# Main.net
KiCad netlist of a schematic drawn in Altium Designer
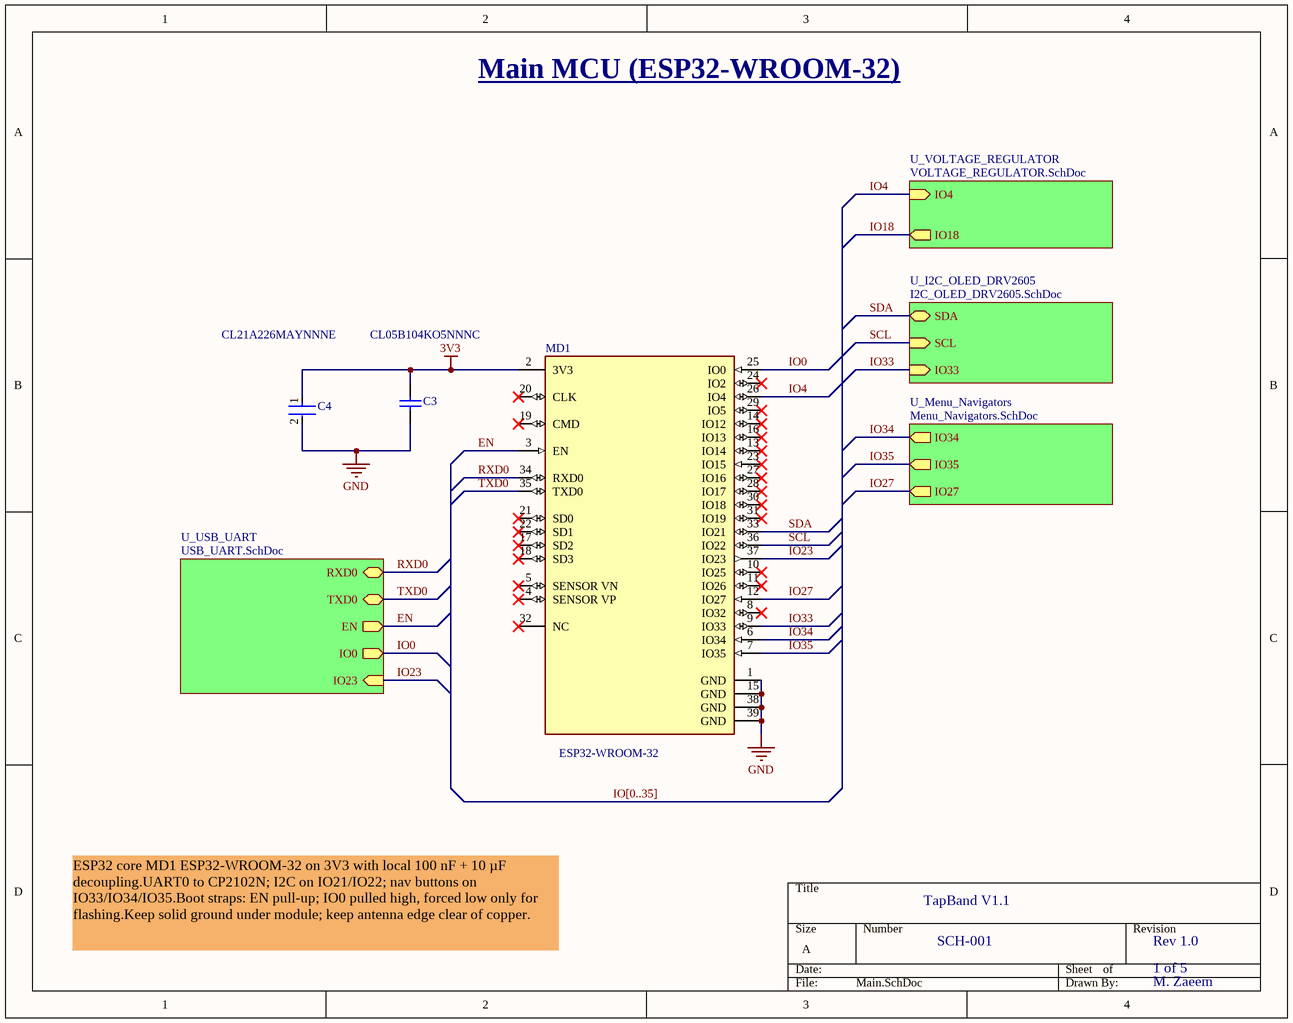
[diagram p0: Main.SchDoc]

(export (version "E")
  (design (tool "Eeschema 10.0.6"))
  (components
    (comp (ref "C3")
      (value "CL05B104KO5NNNC")
      (footprint "CAPC1050X55X23ML05T13")
      (description "Chip Capacitor, 100 nF, +/- 10%, 16 V, -55 to 125 degC, 0402 (1005 Metric), RoHS, Tape and Reel")
      (fields (field (name "MANUFACTURER") "Samsung Electro-Mechanics"))
      (libsource (lib "Altium Content Vault") (part "CAP-NP-2"))
    )
    (comp (ref "C4")
      (value "CL21A226MAYNNNE")
      (footprint "FP-CL21-IPC_C")
      (description "CL21 Series 0805 22uF 25V ±20% Tolerance X5R Multilayer Ceramic Chip Capacitor")
      (libsource (lib "Altium Content Vault") (part "b4654b650e69147ec39a6b967a45e02"))
    )
    (comp (ref "MD1")
      (value "ESP32-WROOM-32")
      (footprint "FP-ESP32-WROOM-32-MFG")
      (description "RX TXRX MOD WIFI SURFACE MOUNT")
      (libsource (lib "Altium Content Vault") (part "ee866abf0b6c51247b7f5cdebf2f250"))
    )
  )
  (nets
    (net (code "29") (name "/EN") (class "Default")
      (node (ref "MD1") (pin "3") (pinfunction "EN_3") (pintype "input"))
    )
    (net (code "30") (name "/IO0") (class "Default")
      (node (ref "MD1") (pin "25") (pinfunction "IO0_25") (pintype "input"))
    )
    (net (code "31") (name "/IO4") (class "Default")
      (node (ref "MD1") (pin "26") (pinfunction "IO4_26") (pintype "bidirectional"))
    )
    (net (code "33") (name "/IO23") (class "Default")
      (node (ref "MD1") (pin "37") (pinfunction "IO23_37") (pintype "output"))
    )
    (net (code "34") (name "/IO27") (class "Default")
      (node (ref "MD1") (pin "12") (pinfunction "IO27_12") (pintype "input"))
    )
    (net (code "35") (name "/IO33") (class "Default")
      (node (ref "MD1") (pin "9") (pinfunction "IO33_9") (pintype "bidirectional"))
    )
    (net (code "36") (name "/IO34") (class "Default")
      (node (ref "MD1") (pin "6") (pinfunction "IO34_6") (pintype "input"))
    )
    (net (code "37") (name "/IO35") (class "Default")
      (node (ref "MD1") (pin "7") (pinfunction "IO35_7") (pintype "input"))
    )
    (net (code "39") (name "/RXD0") (class "Default")
      (node (ref "MD1") (pin "34") (pinfunction "RXD0_34") (pintype "bidirectional"))
    )
    (net (code "40") (name "/SCL") (class "Default")
      (node (ref "MD1") (pin "36") (pinfunction "IO22_36") (pintype "bidirectional"))
    )
    (net (code "41") (name "/SDA") (class "Default")
      (node (ref "MD1") (pin "33") (pinfunction "IO21_33") (pintype "bidirectional"))
    )
    (net (code "42") (name "/TXD0") (class "Default")
      (node (ref "MD1") (pin "35") (pinfunction "TXD0_35") (pintype "bidirectional"))
    )
    (net (code "43") (name "3V3") (class "Default")
      (node (ref "C3") (pin "2") (pinfunction "2_2") (pintype "passive"))
      (node (ref "C4") (pin "1") (pinfunction "1_1") (pintype "passive"))
      (node (ref "MD1") (pin "2") (pinfunction "3V3_2") (pintype "power_in"))
    )
    (net (code "44") (name "GND") (class "Default")
      (node (ref "C3") (pin "1") (pinfunction "1_1") (pintype "passive"))
      (node (ref "C4") (pin "2") (pinfunction "2_2") (pintype "passive"))
      (node (ref "MD1") (pin "1") (pinfunction "GND_1") (pintype "power_in"))
      (node (ref "MD1") (pin "15") (pinfunction "GND_15") (pintype "power_in"))
      (node (ref "MD1") (pin "38") (pinfunction "GND_38") (pintype "power_in"))
      (node (ref "MD1") (pin "39") (pinfunction "GND_39") (pintype "power_in"))
    )
    (net (code "45") (name "unconnected-(MD1-CLK-Pad20)") (class "Default")
      (node (ref "MD1") (pin "20") (pinfunction "CLK_20") (pintype "bidirectional+no_connect"))
    )
    (net (code "46") (name "unconnected-(MD1-CMD-Pad19)") (class "Default")
      (node (ref "MD1") (pin "19") (pinfunction "CMD_19") (pintype "bidirectional+no_connect"))
    )
    (net (code "47") (name "unconnected-(MD1-IO2-Pad24)") (class "Default")
      (node (ref "MD1") (pin "24") (pinfunction "IO2_24") (pintype "bidirectional+no_connect"))
    )
    (net (code "48") (name "unconnected-(MD1-IO5-Pad29)") (class "Default")
      (node (ref "MD1") (pin "29") (pinfunction "IO5_29") (pintype "bidirectional+no_connect"))
    )
    (net (code "49") (name "unconnected-(MD1-IO12-Pad14)") (class "Default")
      (node (ref "MD1") (pin "14") (pinfunction "IO12_14") (pintype "bidirectional+no_connect"))
    )
    (net (code "50") (name "unconnected-(MD1-IO13-Pad16)") (class "Default")
      (node (ref "MD1") (pin "16") (pinfunction "IO13_16") (pintype "bidirectional+no_connect"))
    )
    (net (code "51") (name "unconnected-(MD1-IO14-Pad13)") (class "Default")
      (node (ref "MD1") (pin "13") (pinfunction "IO14_13") (pintype "bidirectional+no_connect"))
    )
    (net (code "52") (name "unconnected-(MD1-IO15-Pad23)") (class "Default")
      (node (ref "MD1") (pin "23") (pinfunction "IO15_23") (pintype "input+no_connect"))
    )
    (net (code "53") (name "unconnected-(MD1-IO16-Pad27)") (class "Default")
      (node (ref "MD1") (pin "27") (pinfunction "IO16_27") (pintype "bidirectional+no_connect"))
    )
    (net (code "54") (name "unconnected-(MD1-IO17-Pad28)") (class "Default")
      (node (ref "MD1") (pin "28") (pinfunction "IO17_28") (pintype "bidirectional+no_connect"))
    )
    (net (code "55") (name "unconnected-(MD1-IO18-Pad30)") (class "Default")
      (node (ref "MD1") (pin "30") (pinfunction "IO18_30") (pintype "bidirectional+no_connect"))
    )
    (net (code "56") (name "unconnected-(MD1-IO19-Pad31)") (class "Default")
      (node (ref "MD1") (pin "31") (pinfunction "IO19_31") (pintype "bidirectional+no_connect"))
    )
    (net (code "57") (name "unconnected-(MD1-IO25-Pad10)") (class "Default")
      (node (ref "MD1") (pin "10") (pinfunction "IO25_10") (pintype "bidirectional+no_connect"))
    )
    (net (code "58") (name "unconnected-(MD1-IO26-Pad11)") (class "Default")
      (node (ref "MD1") (pin "11") (pinfunction "IO26_11") (pintype "bidirectional+no_connect"))
    )
    (net (code "59") (name "unconnected-(MD1-IO32-Pad8)") (class "Default")
      (node (ref "MD1") (pin "8") (pinfunction "IO32_8") (pintype "bidirectional+no_connect"))
    )
    (net (code "60") (name "unconnected-(MD1-NC-Pad32)") (class "Default")
      (node (ref "MD1") (pin "32") (pinfunction "NC_32") (pintype "passive+no_connect"))
    )
    (net (code "61") (name "unconnected-(MD1-SD0-Pad21)") (class "Default")
      (node (ref "MD1") (pin "21") (pinfunction "SD0_21") (pintype "bidirectional+no_connect"))
    )
    (net (code "62") (name "unconnected-(MD1-SD1-Pad22)") (class "Default")
      (node (ref "MD1") (pin "22") (pinfunction "SD1_22") (pintype "bidirectional+no_connect"))
    )
    (net (code "63") (name "unconnected-(MD1-SD2-Pad17)") (class "Default")
      (node (ref "MD1") (pin "17") (pinfunction "SD2_17") (pintype "bidirectional+no_connect"))
    )
    (net (code "64") (name "unconnected-(MD1-SD3-Pad18)") (class "Default")
      (node (ref "MD1") (pin "18") (pinfunction "SD3_18") (pintype "bidirectional+no_connect"))
    )
    (net (code "65") (name "unconnected-(MD1-SENSOR_VN-Pad5)") (class "Default")
      (node (ref "MD1") (pin "5") (pinfunction "SENSOR_VN_5") (pintype "bidirectional+no_connect"))
    )
    (net (code "66") (name "unconnected-(MD1-SENSOR_VP-Pad4)") (class "Default")
      (node (ref "MD1") (pin "4") (pinfunction "SENSOR_VP_4") (pintype "bidirectional+no_connect"))
    )
  )
)
